# Led_Strip_23.net
KiCad netlist of a schematic drawn in EAGLE
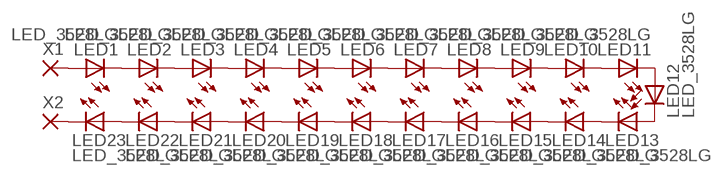
[diagram p0: schematic, sheet 1]

(export (version "E")
  (design (tool "Eeschema 10.0.6"))
  (components
    (comp (ref "LED1")
      (value "LED_3528LG")
      (footprint "eagle-import:LED2835_LG")
      (libsource (lib "eagle-import") (part "LED_3528LG"))
    )
    (comp (ref "LED2")
      (value "LED_3528LG")
      (footprint "eagle-import:LED2835_LG")
      (libsource (lib "eagle-import") (part "LED_3528LG"))
    )
    (comp (ref "LED3")
      (value "LED_3528LG")
      (footprint "eagle-import:LED2835_LG")
      (libsource (lib "eagle-import") (part "LED_3528LG"))
    )
    (comp (ref "LED4")
      (value "LED_3528LG")
      (footprint "eagle-import:LED2835_LG")
      (libsource (lib "eagle-import") (part "LED_3528LG"))
    )
    (comp (ref "LED5")
      (value "LED_3528LG")
      (footprint "eagle-import:LED2835_LG")
      (libsource (lib "eagle-import") (part "LED_3528LG"))
    )
    (comp (ref "LED6")
      (value "LED_3528LG")
      (footprint "eagle-import:LED2835_LG")
      (libsource (lib "eagle-import") (part "LED_3528LG"))
    )
    (comp (ref "LED7")
      (value "LED_3528LG")
      (footprint "eagle-import:LED2835_LG")
      (libsource (lib "eagle-import") (part "LED_3528LG"))
    )
    (comp (ref "LED8")
      (value "LED_3528LG")
      (footprint "eagle-import:LED2835_LG")
      (libsource (lib "eagle-import") (part "LED_3528LG"))
    )
    (comp (ref "LED9")
      (value "LED_3528LG")
      (footprint "eagle-import:LED2835_LG")
      (libsource (lib "eagle-import") (part "LED_3528LG"))
    )
    (comp (ref "LED10")
      (value "LED_3528LG")
      (footprint "eagle-import:LED2835_LG")
      (libsource (lib "eagle-import") (part "LED_3528LG"))
    )
    (comp (ref "LED11")
      (value "LED_3528LG")
      (footprint "eagle-import:LED2835_LG")
      (libsource (lib "eagle-import") (part "LED_3528LG"))
    )
    (comp (ref "LED12")
      (value "LED_3528LG")
      (footprint "eagle-import:LED2835_LG")
      (libsource (lib "eagle-import") (part "LED_3528LG"))
    )
    (comp (ref "LED13")
      (value "LED_3528LG")
      (footprint "eagle-import:LED2835_LG")
      (libsource (lib "eagle-import") (part "LED_3528LG"))
    )
    (comp (ref "LED14")
      (value "LED_3528LG")
      (footprint "eagle-import:LED2835_LG")
      (libsource (lib "eagle-import") (part "LED_3528LG"))
    )
    (comp (ref "LED15")
      (value "LED_3528LG")
      (footprint "eagle-import:LED2835_LG")
      (libsource (lib "eagle-import") (part "LED_3528LG"))
    )
    (comp (ref "LED16")
      (value "LED_3528LG")
      (footprint "eagle-import:LED2835_LG")
      (libsource (lib "eagle-import") (part "LED_3528LG"))
    )
    (comp (ref "LED17")
      (value "LED_3528LG")
      (footprint "eagle-import:LED2835_LG")
      (libsource (lib "eagle-import") (part "LED_3528LG"))
    )
    (comp (ref "LED18")
      (value "LED_3528LG")
      (footprint "eagle-import:LED2835_LG")
      (libsource (lib "eagle-import") (part "LED_3528LG"))
    )
    (comp (ref "LED19")
      (value "LED_3528LG")
      (footprint "eagle-import:LED2835_LG")
      (libsource (lib "eagle-import") (part "LED_3528LG"))
    )
    (comp (ref "LED20")
      (value "LED_3528LG")
      (footprint "eagle-import:LED2835_LG")
      (libsource (lib "eagle-import") (part "LED_3528LG"))
    )
    (comp (ref "LED21")
      (value "LED_3528LG")
      (footprint "eagle-import:LED2835_LG")
      (libsource (lib "eagle-import") (part "LED_3528LG"))
    )
    (comp (ref "LED22")
      (value "LED_3528LG")
      (footprint "eagle-import:LED2835_LG")
      (libsource (lib "eagle-import") (part "LED_3528LG"))
    )
    (comp (ref "LED23")
      (value "LED_3528LG")
      (footprint "eagle-import:LED2835_LG")
      (libsource (lib "eagle-import") (part "LED_3528LG"))
    )
    (comp (ref "X1")
      (value "WIREPAD-SMD2")
      (footprint "eagle-import:PAD-1.27X2.54")
      (libsource (lib "eagle-import") (part "WIREPAD-SMD2"))
    )
    (comp (ref "X2")
      (value "WIREPAD-SMD2")
      (footprint "eagle-import:PAD-1.27X2.54")
      (libsource (lib "eagle-import") (part "WIREPAD-SMD2"))
    )
  )
  (nets
    (net (code "1") (name "Net-(LED1-PadC)") (class "Default")
      (node (ref "LED1") (pin "C") (pinfunction "C_C") (pintype "passive"))
      (node (ref "LED2") (pin "A") (pinfunction "A_A") (pintype "passive"))
    )
    (net (code "2") (name "Net-(LED2-PadC)") (class "Default")
      (node (ref "LED2") (pin "C") (pinfunction "C_C") (pintype "passive"))
      (node (ref "LED3") (pin "A") (pinfunction "A_A") (pintype "passive"))
    )
    (net (code "3") (name "Net-(LED3-PadC)") (class "Default")
      (node (ref "LED3") (pin "C") (pinfunction "C_C") (pintype "passive"))
      (node (ref "LED4") (pin "A") (pinfunction "A_A") (pintype "passive"))
    )
    (net (code "4") (name "Net-(LED4-PadC)") (class "Default")
      (node (ref "LED4") (pin "C") (pinfunction "C_C") (pintype "passive"))
      (node (ref "LED5") (pin "A") (pinfunction "A_A") (pintype "passive"))
    )
    (net (code "5") (name "Net-(LED5-PadC)") (class "Default")
      (node (ref "LED5") (pin "C") (pinfunction "C_C") (pintype "passive"))
      (node (ref "LED6") (pin "A") (pinfunction "A_A") (pintype "passive"))
    )
    (net (code "6") (name "Net-(LED6-PadC)") (class "Default")
      (node (ref "LED6") (pin "C") (pinfunction "C_C") (pintype "passive"))
      (node (ref "LED7") (pin "A") (pinfunction "A_A") (pintype "passive"))
    )
    (net (code "7") (name "Net-(LED7-PadC)") (class "Default")
      (node (ref "LED7") (pin "C") (pinfunction "C_C") (pintype "passive"))
      (node (ref "LED8") (pin "A") (pinfunction "A_A") (pintype "passive"))
    )
    (net (code "8") (name "Net-(LED8-PadC)") (class "Default")
      (node (ref "LED8") (pin "C") (pinfunction "C_C") (pintype "passive"))
      (node (ref "LED9") (pin "A") (pinfunction "A_A") (pintype "passive"))
    )
    (net (code "9") (name "Net-(LED10-PadA)") (class "Default")
      (node (ref "LED10") (pin "A") (pinfunction "A_A") (pintype "passive"))
      (node (ref "LED9") (pin "C") (pinfunction "C_C") (pintype "passive"))
    )
    (net (code "10") (name "Net-(LED10-PadC)") (class "Default")
      (node (ref "LED10") (pin "C") (pinfunction "C_C") (pintype "passive"))
      (node (ref "LED11") (pin "A") (pinfunction "A_A") (pintype "passive"))
    )
    (net (code "11") (name "Net-(LED11-PadC)") (class "Default")
      (node (ref "LED11") (pin "C") (pinfunction "C_C") (pintype "passive"))
      (node (ref "LED12") (pin "A") (pinfunction "A_A") (pintype "passive"))
    )
    (net (code "12") (name "Net-(LED12-PadC)") (class "Default")
      (node (ref "LED12") (pin "C") (pinfunction "C_C") (pintype "passive"))
      (node (ref "LED13") (pin "A") (pinfunction "A_A") (pintype "passive"))
    )
    (net (code "13") (name "Net-(LED13-PadC)") (class "Default")
      (node (ref "LED13") (pin "C") (pinfunction "C_C") (pintype "passive"))
      (node (ref "LED14") (pin "A") (pinfunction "A_A") (pintype "passive"))
    )
    (net (code "14") (name "Net-(LED14-PadC)") (class "Default")
      (node (ref "LED14") (pin "C") (pinfunction "C_C") (pintype "passive"))
      (node (ref "LED15") (pin "A") (pinfunction "A_A") (pintype "passive"))
    )
    (net (code "15") (name "Net-(LED15-PadC)") (class "Default")
      (node (ref "LED15") (pin "C") (pinfunction "C_C") (pintype "passive"))
      (node (ref "LED16") (pin "A") (pinfunction "A_A") (pintype "passive"))
    )
    (net (code "16") (name "Net-(LED16-PadC)") (class "Default")
      (node (ref "LED16") (pin "C") (pinfunction "C_C") (pintype "passive"))
      (node (ref "LED17") (pin "A") (pinfunction "A_A") (pintype "passive"))
    )
    (net (code "17") (name "Net-(LED17-PadC)") (class "Default")
      (node (ref "LED17") (pin "C") (pinfunction "C_C") (pintype "passive"))
      (node (ref "LED18") (pin "A") (pinfunction "A_A") (pintype "passive"))
    )
    (net (code "18") (name "Net-(LED18-PadC)") (class "Default")
      (node (ref "LED18") (pin "C") (pinfunction "C_C") (pintype "passive"))
      (node (ref "LED19") (pin "A") (pinfunction "A_A") (pintype "passive"))
    )
    (net (code "19") (name "Net-(LED19-PadC)") (class "Default")
      (node (ref "LED19") (pin "C") (pinfunction "C_C") (pintype "passive"))
      (node (ref "LED20") (pin "A") (pinfunction "A_A") (pintype "passive"))
    )
    (net (code "20") (name "Net-(LED20-PadC)") (class "Default")
      (node (ref "LED20") (pin "C") (pinfunction "C_C") (pintype "passive"))
      (node (ref "LED21") (pin "A") (pinfunction "A_A") (pintype "passive"))
    )
    (net (code "21") (name "Net-(LED21-PadC)") (class "Default")
      (node (ref "LED21") (pin "C") (pinfunction "C_C") (pintype "passive"))
      (node (ref "LED22") (pin "A") (pinfunction "A_A") (pintype "passive"))
    )
    (net (code "22") (name "Net-(LED22-PadC)") (class "Default")
      (node (ref "LED22") (pin "C") (pinfunction "C_C") (pintype "passive"))
      (node (ref "LED23") (pin "A") (pinfunction "A_A") (pintype "passive"))
    )
    (net (code "23") (name "Net-(X1-P)") (class "Default")
      (node (ref "LED1") (pin "A") (pinfunction "A_A") (pintype "passive"))
      (node (ref "X1") (pin "P$1") (pinfunction "P_P$1") (pintype "passive"))
    )
    (net (code "24") (name "Net-(X2-P)") (class "Default")
      (node (ref "LED23") (pin "C") (pinfunction "C_C") (pintype "passive"))
      (node (ref "X2") (pin "P$1") (pinfunction "P_P$1") (pintype "passive"))
    )
  )
)
